# Door_Actuator.net
KiCad netlist of a schematic drawn in Altium Designer
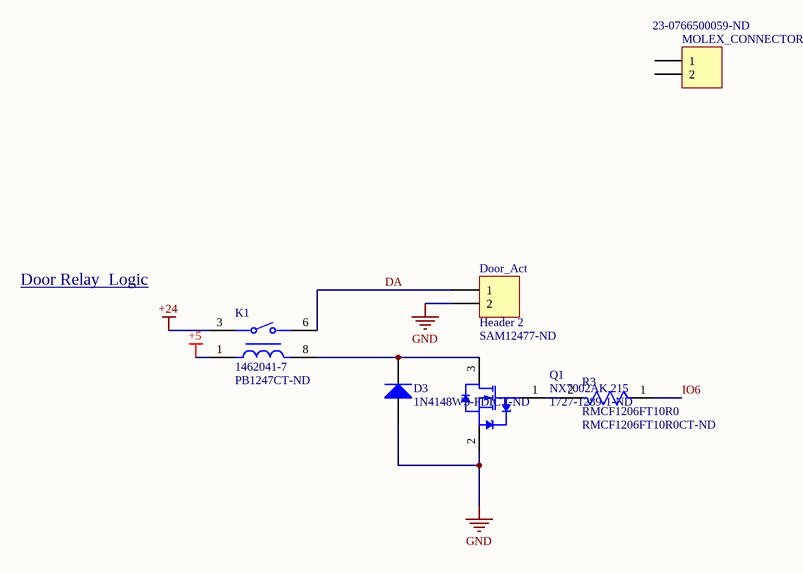
[diagram p0: Door_Actuator.SchDoc]

(export (version "E")
  (design (tool "Eeschema 10.0.6"))
  (components
    (comp (ref "D3")
      (value "1N4148WS-7-F")
      (footprint "DIOD-SOD323-2-A_V")
      (description "Fast Switching Diode, 75 V, 0.3 A, -65 to 150 degC, 2-Pin SOD323, RoHS, Tape and Reel")
      (fields
        (field (name "SUPPLIER PART NUMBER 1") "1N4148WS-FDICT-ND")
        (field (name "MANUFACTURER") "Diodes")
      )
      (libsource (lib "Altium Content Vault") (part "D-AK-2"))
    )
    (comp (ref "Door_Act")
      (value "Header 2")
      (footprint "HDR1X2")
      (fields
        (field (name "SUPPLIER PART NUMBER 1") "SAM12477-ND")
        (field (name "MANUFACTURER") "Samtec")
        (field (name "MANUFACTURER PART NUMBER") "CES-102-01-G-S")
      )
      (libsource (lib "Miscellaneous Connectors") (part "Header 2"))
    )
    (comp (ref "K1")
      (value "1462041-7")
      (footprint "FP-1462041-7-MFG")
      (description "RELAY TELECOM SPST 2A 5VDC")
      (fields
        (field (name "OCTOPART") "https://octopart.com/1462041-7-te+connectivity-42558739")
        (field (name "MANUFACTURER") "TE Connectivity")
        (field (name "SUPPLIER PART NUMBER 1") "PB1247CT-ND")
      )
      (libsource (lib "Altium Content Vault") (part "be76edbf9588da4ea333a563391ad18"))
    )
    (comp (ref "MOLEX_CONNECTOR")
      (value "~")
      (footprint "HDR1X2")
      (description ".093IN Pwr Connector Kit Single Row Panel Mnt Plug & Recept; 4 Ckt")
      (fields
        (field (name "SUPPLIER PART NUMBER 1") "23-0766500059-ND")
        (field (name "MANUFACTURER") "Molex")
        (field (name "MANUFACTURER PART NUMBER") "76650-0059")
      )
      (libsource (lib "Miscellaneous Connectors") (part "Header 2"))
    )
    (comp (ref "Q1")
      (value "NX7002AK,215")
      (footprint "NXP-SOT23_L")
      (description "Single N-Channel Trench MOSFET, 60 V, -55 to 150 degC, 3-Pin SOT23, Tape and Reel")
      (fields
        (field (name "MANUFACTURER") "NXP Semiconductors")
        (field (name "SUPPLIER PART NUMBER 1") "1727-1289-1-ND")
      )
      (libsource (lib "Altium Content Vault") (part "NXP-NMOS-GSD-3"))
    )
    (comp (ref "R3")
      (value "RMCF1206FT10R0")
      (footprint "FP-RMCF1206-IPC_C")
      (description "RES 10 OHM 1% 1/4W 1206")
      (fields
        (field (name "TOLERANCE") "1%")
        (field (name "SUPPLIER PART NUMBER 1") "RMCF1206FT10R0CT-ND")
        (field (name "MANUFACTURER") "Stackpole Electronics")
      )
      (libsource (lib "Altium Content Vault") (part "1029c3af85768c4190bb7ad29bc67b5"))
    )
  )
  (nets
    (net (code "1") (name "+5") (class "Default")
      (node (ref "K1") (pin "1") (pinfunction "1_1") (pintype "passive"))
    )
    (net (code "2") (name "+24") (class "Default")
      (node (ref "K1") (pin "3") (pinfunction "3_3") (pintype "passive"))
    )
    (net (code "3") (name "/DA") (class "Default")
      (node (ref "Door_Act") (pin "1") (pinfunction "1_1") (pintype "passive"))
      (node (ref "K1") (pin "6") (pinfunction "6_6") (pintype "passive"))
    )
    (net (code "4") (name "/IO6") (class "Default")
      (node (ref "R3") (pin "1") (pinfunction "1_1") (pintype "passive"))
    )
    (net (code "5") (name "GND") (class "Default")
      (node (ref "D3") (pin "1") (pinfunction "A_1") (pintype "passive"))
      (node (ref "Door_Act") (pin "2") (pinfunction "2_2") (pintype "passive"))
      (node (ref "Q1") (pin "2") (pinfunction "S_2") (pintype "passive"))
    )
    (net (code "6") (name "Net-(D3-K)") (class "Default")
      (node (ref "D3") (pin "2") (pinfunction "K_2") (pintype "passive"))
      (node (ref "K1") (pin "8") (pinfunction "8_8") (pintype "passive"))
      (node (ref "Q1") (pin "3") (pinfunction "D_3") (pintype "passive"))
    )
    (net (code "7") (name "Net-(Q1-G)") (class "Default")
      (node (ref "Q1") (pin "1") (pinfunction "G_1") (pintype "passive"))
      (node (ref "R3") (pin "2") (pinfunction "2_2") (pintype "passive"))
    )
    (net (code "8") (name "unconnected-(MOLEX_CONNECTOR-Pad1)") (class "Default")
      (node (ref "MOLEX_CONNECTOR") (pin "1") (pinfunction "1_1") (pintype "passive"))
    )
    (net (code "9") (name "unconnected-(MOLEX_CONNECTOR-Pad2)") (class "Default")
      (node (ref "MOLEX_CONNECTOR") (pin "2") (pinfunction "2_2") (pintype "passive"))
    )
  )
)
